# Power.net
KiCad netlist of a schematic drawn in Altium Designer
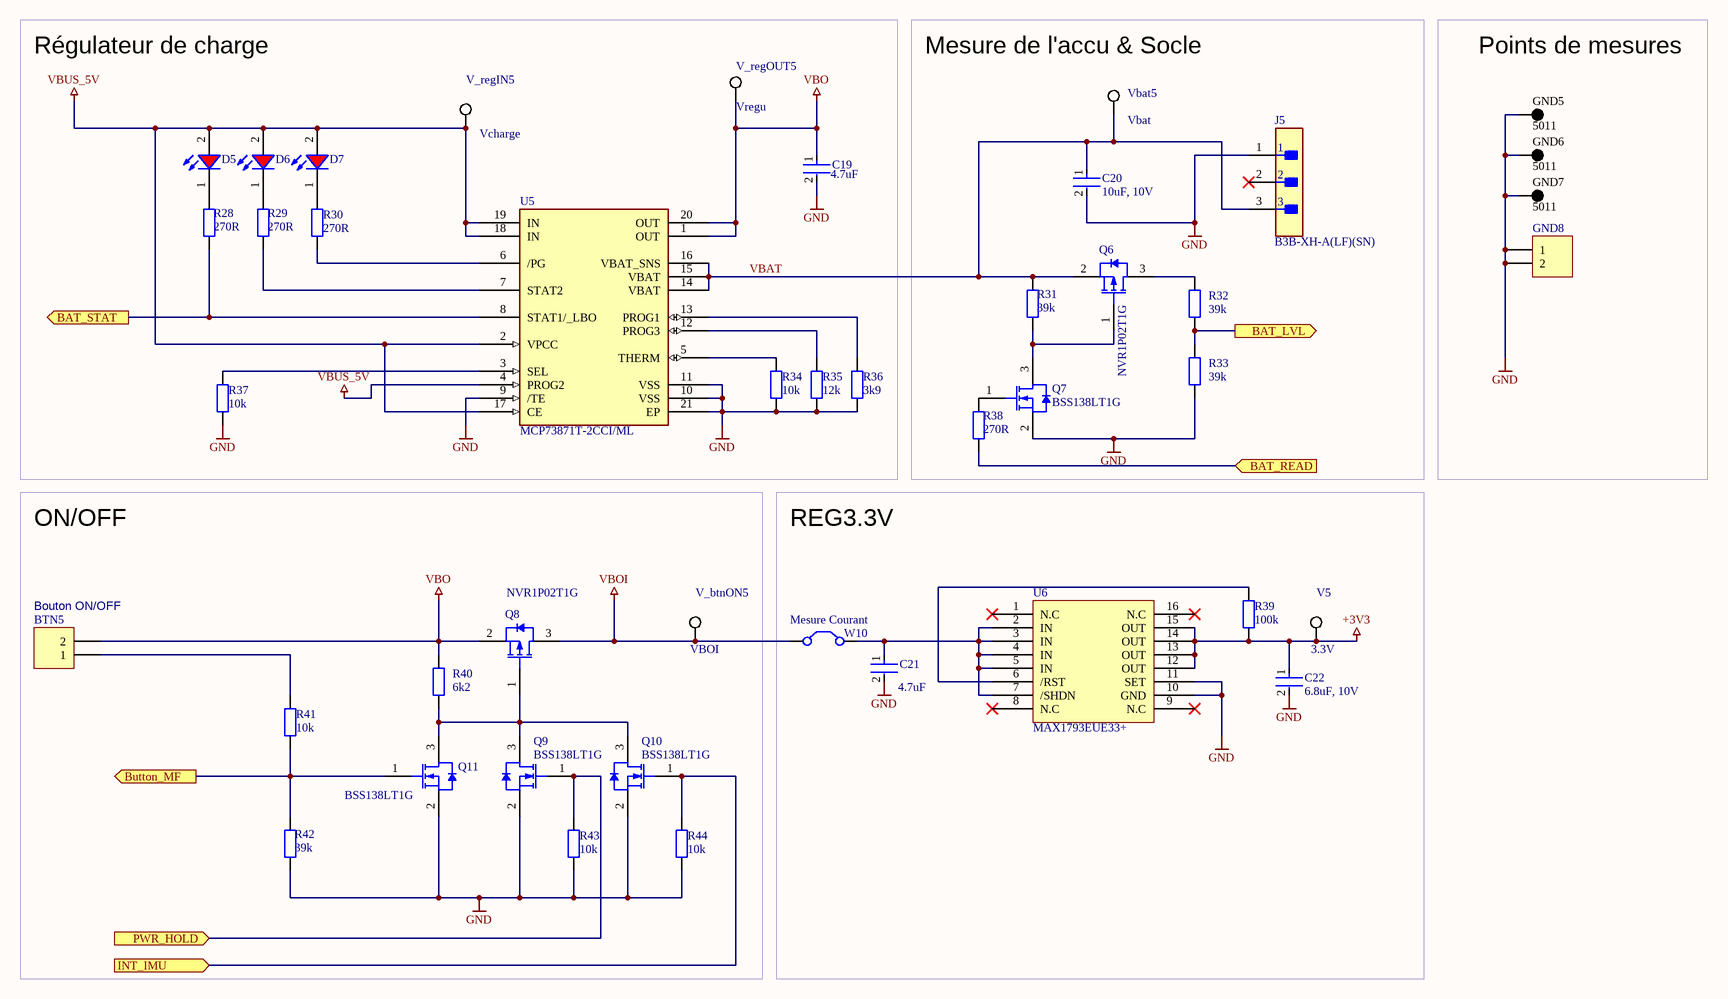
[diagram p0: Power.SchDoc]

(export (version "E")
  (design (tool "Eeschema 10.0.6"))
  (components
    (comp (ref "BTN5")
      (value "Button connector")
      (footprint "HDR1X2")
      (description "Header, 2-Pin")
      (fields (field (name "PUBLISHER") "Altium Limited"))
      (libsource (lib "") (part "Header 2_1"))
    )
    (comp (ref "C19")
      (value "4.7uF, 35V")
      (footprint "Cap_0805")
      (description "Multilayer Ceramic Capacitors 4.7μF ±10% 35V X7R SMD 0805")
      (fields (field (name "TOLERANCE") "10%") (field (name "CAPACITANCE") "4.7uF"))
      (libsource (lib "2121_Robot3roues_V2.0") (part "b4654b650e69147ec39a6b967a45e02"))
    )
    (comp (ref "C20")
      (value "10uF, 10V")
      (footprint "Cap_0805")
      (description "CAP CER 10UF 10V X5R 0805")
      (fields (field (name "TOLERANCE") "10%") (field (name "MANUFACTURER PART NUMBER") "C0805C106K8PACTU"))
      (libsource (lib "2121_Robot3roues_V2.0") (part "11868f565c42a9108669ba33697ecf6"))
    )
    (comp (ref "C21")
      (value "4.7uF, 35V")
      (footprint "Cap_0805")
      (description "Multilayer Ceramic Capacitors 4.7μF ±10% 35V X7R SMD 0805")
      (fields (field (name "TOLERANCE") "10%") (field (name "CAPACITANCE") "4.7uF"))
      (libsource (lib "2121_Robot3roues_V2.0") (part "b4654b650e69147ec39a6b967a45e02"))
    )
    (comp (ref "C22")
      (value "6.8uF, 10V")
      (footprint "Cap_0805")
      (description "Cap Ceramic 6.8uF 10V X5R 20% Pad SMD 0805 +85°C Automotive T/R")
      (fields (field (name "TOLERANCE") "20%"))
      (libsource (lib "2121_Robot3roues_V2.0") (part "b4654b650e69147ec39a6b967a45e02"))
    )
    (comp (ref "D5")
      (value "Super Red, 1.9 V")
      (footprint "WL-SMCW_0805_150080xx75000")
      (description "SMT Mono-color Chip LED Waterclear WL-SMCW, size 0805, Super Red, 1.9 V, 140 deg, 60 mcd")
      (fields (field (name "PART NUMBER") "150080SS75000") (field (name "PUBLISHER") "Wurth Elektronik"))
      (libsource (lib "VPA_v2b") (part "150080SS75000"))
    )
    (comp (ref "D6")
      (value "Super Red, 1.9 V")
      (footprint "WL-SMCW_0805_150080xx75000")
      (description "SMT Mono-color Chip LED Waterclear WL-SMCW, size 0805, Super Red, 1.9 V, 140 deg, 60 mcd")
      (fields (field (name "PART NUMBER") "150080SS75000") (field (name "PUBLISHER") "Wurth Elektronik"))
      (libsource (lib "VPA_v2b") (part "150080SS75000"))
    )
    (comp (ref "D7")
      (value "Super Red, 1.9 V")
      (footprint "WL-SMCW_0805_150080xx75000")
      (description "SMT Mono-color Chip LED Waterclear WL-SMCW, size 0805, Super Red, 1.9 V, 140 deg, 60 mcd")
      (fields (field (name "PART NUMBER") "150080SS75000") (field (name "PUBLISHER") "Wurth Elektronik"))
      (libsource (lib "VPA_v2b") (part "150080SS75000"))
    )
    (comp (ref "GND5")
      (value "5011")
      (footprint "KSTN-5011_V")
      (description "Test Point, Black, Through Hole, RoHS, Bulk")
      (fields (field (name "MANUFACTURER") "Keystone"))
      (libsource (lib "Altium Content Vault") (part "TESTPOINT_BLACK"))
    )
    (comp (ref "GND6")
      (value "5011")
      (footprint "KSTN-5011_V")
      (description "Test Point, Black, Through Hole, RoHS, Bulk")
      (fields (field (name "MANUFACTURER") "Keystone"))
      (libsource (lib "Altium Content Vault") (part "TESTPOINT_BLACK"))
    )
    (comp (ref "GND7")
      (value "5011")
      (footprint "KSTN-5011_V")
      (description "Test Point, Black, Through Hole, RoHS, Bulk")
      (fields (field (name "MANUFACTURER") "Keystone"))
      (libsource (lib "Altium Content Vault") (part "TESTPOINT_BLACK"))
    )
    (comp (ref "GND8")
      (value "Header 2")
      (footprint "HDR1X2")
      (description "Header, 2-Pin")
      (fields (field (name "PUBLISHER") "Altium Limited"))
      (libsource (lib "Miscellaneous Connectors") (part "Header 2"))
    )
    (comp (ref "J5")
      (value "B3B-XH-A(LF)(SN)")
      (footprint "FP-B3B-XH-A_LF_SN-MFG")
      (description "CONN HEADER VERT 3POS 2.5MM")
      (libsource (lib "Altium Content Vault") (part "0d3f023dd272f625e17a2be33dea85f"))
    )
    (comp (ref "Q6")
      (value "NVR1P02T1G")
      (footprint "ONSC-SOT-23-3-318-08_V")
      (description "Power MOSFET, -20 V, -1 A, P-Channel, 3-Pin SOT-23, Pb-Free, Tape and Reel")
      (fields (field (name "MANUFACTURER") "On Semiconductor"))
      (libsource (lib "Altium Content Vault") (part "ONSC-PMOS-G1S2D3-3_D"))
    )
    (comp (ref "Q7")
      (value "BSS138LT1G")
      (footprint "ONSC-SOT-23-3-318-08_V")
      (description "Power MOSFET, 200 mA, 50 V, N-Channel, 3-Pin SOT-23, Pb-Free, Tape and Reel")
      (fields (field (name "MANUFACTURER") "On Semiconductor"))
      (libsource (lib "Altium Content Vault") (part "ONSC-NMOS-G1S2D3-3"))
    )
    (comp (ref "Q8")
      (value "NVR1P02T1G")
      (footprint "ONSC-SOT-23-3-318-08_V")
      (description "Power MOSFET, -20 V, -1 A, P-Channel, 3-Pin SOT-23, Pb-Free, Tape and Reel")
      (fields (field (name "MANUFACTURER") "On Semiconductor"))
      (libsource (lib "Altium Content Vault") (part "ONSC-PMOS-G1S2D3-3_D"))
    )
    (comp (ref "Q9")
      (value "BSS138LT1G")
      (footprint "ONSC-SOT-23-3-318-08_V")
      (description "Power MOSFET, 200 mA, 50 V, N-Channel, 3-Pin SOT-23, Pb-Free, Tape and Reel")
      (fields (field (name "MANUFACTURER") "On Semiconductor"))
      (libsource (lib "Altium Content Vault") (part "ONSC-NMOS-G1S2D3-3"))
    )
    (comp (ref "Q10")
      (value "BSS138LT1G")
      (footprint "ONSC-SOT-23-3-318-08_V")
      (description "Power MOSFET, 200 mA, 50 V, N-Channel, 3-Pin SOT-23, Pb-Free, Tape and Reel")
      (fields (field (name "MANUFACTURER") "On Semiconductor"))
      (libsource (lib "Altium Content Vault") (part "ONSC-NMOS-G1S2D3-3"))
    )
    (comp (ref "Q11")
      (value "BSS138LT1G")
      (footprint "ONSC-SOT-23-3-318-08_V")
      (description "Power MOSFET, 200 mA, 50 V, N-Channel, 3-Pin SOT-23, Pb-Free, Tape and Reel")
      (fields (field (name "MANUFACTURER") "On Semiconductor"))
      (libsource (lib "Altium Content Vault") (part "ONSC-NMOS-G1S2D3-3"))
    )
    (comp (ref "R28")
      (value "270R")
      (footprint "RES_0805")
      (description "Res 0805")
      (fields (field (name "PART NUMBER") "ERJ6ENF2703V") (field (name "MANUFACTURER") "Panasonic"))
      (libsource (lib "2121_Robot3roues_V2.0") (part "RES"))
    )
    (comp (ref "R29")
      (value "270R")
      (footprint "RES_0805")
      (description "Res 0805")
      (fields (field (name "PART NUMBER") "ERJ6ENF2703V") (field (name "MANUFACTURER") "Panasonic"))
      (libsource (lib "2121_Robot3roues_V2.0") (part "RES"))
    )
    (comp (ref "R30")
      (value "270R")
      (footprint "RES_0805")
      (description "Res 0805")
      (fields (field (name "PART NUMBER") "ERJ6ENF2703V") (field (name "MANUFACTURER") "Panasonic"))
      (libsource (lib "") (part "RES_1"))
    )
    (comp (ref "R31")
      (value "39k")
      (footprint "RES_0805")
      (description "Res 0805")
      (fields (field (name "PART NUMBER") "ERJ-6GEYJ393V") (field (name "MANUFACTURER") "Panasonic"))
      (libsource (lib "2121_Robot3roues_V2.0") (part "RES"))
    )
    (comp (ref "R32")
      (value "39k")
      (footprint "RES_0805")
      (description "Res 0805")
      (fields (field (name "PART NUMBER") "ERJ-6GEYJ393V") (field (name "MANUFACTURER") "Panasonic"))
      (libsource (lib "2121_Robot3roues_V2.0") (part "RES"))
    )
    (comp (ref "R33")
      (value "39k")
      (footprint "RES_0805")
      (description "Res 0805")
      (fields (field (name "PART NUMBER") "ERJ-6GEYJ393V") (field (name "MANUFACTURER") "Panasonic"))
      (libsource (lib "2121_Robot3roues_V2.0") (part "RES"))
    )
    (comp (ref "R34")
      (value "10k")
      (footprint "RES_0805")
      (description "Res 0805")
      (fields (field (name "MANUFACTURER") "Panasonic") (field (name "PART NUMBER") "ERJ-6ENF1002V"))
      (libsource (lib "2121_Robot3roues_V2.0") (part "RES"))
    )
    (comp (ref "R35")
      (value "12k")
      (footprint "RES_0805")
      (description "Res 0805")
      (fields (field (name "MANUFACTURER") "Vishay Dale") (field (name "PART NUMBER") "CRCW08055K60JNEA"))
      (libsource (lib "2121_Robot3roues_V2.0") (part "RES"))
    )
    (comp (ref "R36")
      (value "3k9")
      (footprint "RES_0805")
      (description "Res 0805")
      (fields (field (name "PART NUMBER") "CRCW08051K00FKEA") (field (name "MANUFACTURER") "Vishay Dale"))
      (libsource (lib "2121_Robot3roues_V2.0") (part "RES"))
    )
    (comp (ref "R37")
      (value "10k")
      (footprint "RES_0805")
      (description "Res 0805")
      (fields (field (name "MANUFACTURER") "Panasonic") (field (name "PART NUMBER") "ERJ-6ENF1002V"))
      (libsource (lib "2121_Robot3roues_V2.0") (part "RES"))
    )
    (comp (ref "R38")
      (value "270R")
      (footprint "RES_0805")
      (description "Res 0805")
      (fields (field (name "PART NUMBER") "ERJ6ENF2703V") (field (name "MANUFACTURER") "Panasonic"))
      (libsource (lib "2121_Robot3roues_V2.0") (part "RES"))
    )
    (comp (ref "R39")
      (value "100k")
      (footprint "RES_0805")
      (description "Res 0805")
      (fields (field (name "MANUFACTURER") "Panasonic") (field (name "PART NUMBER") "ERJ-P06J104V"))
      (libsource (lib "2121_Robot3roues_V2.0") (part "RES"))
    )
    (comp (ref "R40")
      (value "6k2")
      (footprint "RES_0805")
      (description "Res 0805")
      (fields (field (name "PART NUMBER") "ERJ6ENF6201V") (field (name "MANUFACTURER") "Panasonic"))
      (libsource (lib "2121_Robot3roues_V2.0") (part "RES"))
    )
    (comp (ref "R41")
      (value "10k")
      (footprint "RES_0805")
      (description "Res 0805")
      (fields (field (name "MANUFACTURER") "Panasonic") (field (name "PART NUMBER") "ERJ-6ENF1002V"))
      (libsource (lib "2121_Robot3roues_V2.0") (part "RES"))
    )
    (comp (ref "R42")
      (value "39k")
      (footprint "RES_0805")
      (description "Res 0805")
      (fields (field (name "PART NUMBER") "ERJ-6GEYJ393V") (field (name "MANUFACTURER") "Panasonic"))
      (libsource (lib "2121_Robot3roues_V2.0") (part "RES"))
    )
    (comp (ref "R43")
      (value "10k")
      (footprint "RES_0805")
      (description "Res 0805")
      (fields (field (name "MANUFACTURER") "Panasonic") (field (name "PART NUMBER") "ERJ-6ENF1002V"))
      (libsource (lib "2121_Robot3roues_V2.0") (part "RES"))
    )
    (comp (ref "R44")
      (value "10k")
      (footprint "RES_0805")
      (description "Res 0805")
      (fields (field (name "MANUFACTURER") "Panasonic") (field (name "PART NUMBER") "ERJ-6ENF1002V"))
      (libsource (lib "2121_Robot3roues_V2.0") (part "RES"))
    )
    (comp (ref "U5")
      (value "MCP73871T-2CCI/ML")
      (footprint "Microchip_C04-126_IPC_B")
      (description "Charger IC Lithium Ion/Polymer 20-QFN _4x4_")
      (fields (field (name "MF") "Microchip") (field (name "DIGI-KEY_PART_NUMBER") "MCP73871T-2CCI/MLCT-ND"))
      (libsource (lib "2221-LIB") (part "MCP73871T-2CCI/ML"))
    )
    (comp (ref "U6")
      (value "MAX1793EUE33+")
      (footprint "TSOP65P640X110_HS-17N")
      (libsource (lib "2221-LIB") (part "MAX1793EUE33+"))
    )
    (comp (ref "V5")
      (value "3.3V")
      (footprint "KSTN-5019_V")
      (description "Test Point, 1 Position SMD, RoHS, Tape and Reel")
      (libsource (lib "Altium Content Vault") (part "TESTPOINT_WHITE"))
    )
    (comp (ref "Vbat5")
      (value "Vbat")
      (footprint "KSTN-5019_V")
      (description "Test Point, 1 Position SMD, RoHS, Tape and Reel")
      (libsource (lib "Altium Content Vault") (part "TESTPOINT_WHITE"))
    )
    (comp (ref "V_btnON5")
      (value "VBOI")
      (footprint "KSTN-5019_V")
      (description "Test Point, 1 Position SMD, RoHS, Tape and Reel")
      (libsource (lib "Altium Content Vault") (part "TESTPOINT_WHITE"))
    )
    (comp (ref "V_regIN5")
      (value "Vcharge")
      (footprint "KSTN-5019_V")
      (description "Test Point, 1 Position SMD, RoHS, Tape and Reel")
      (libsource (lib "Altium Content Vault") (part "TESTPOINT_WHITE"))
    )
    (comp (ref "V_regOUT5")
      (value "Vregu")
      (footprint "KSTN-5019_V")
      (description "Test Point, 1 Position SMD, RoHS, Tape and Reel")
      (libsource (lib "Altium Content Vault") (part "TESTPOINT_WHITE"))
    )
    (comp (ref "W10")
      (value "Jumper")
      (footprint "JUMPER")
      (description "Jumper Wire")
      (fields (field (name "PUBLISHER") "Altium Limited"))
      (libsource (lib "Miscellaneous Devices") (part "Jumper"))
    )
  )
  (nets
    (net (code "1") (name "+3V3") (class "Default")
      (node (ref "C22") (pin "1") (pinfunction "1_1") (pintype "passive"))
      (node (ref "R39") (pin "1") (pinfunction "1_1") (pintype "passive"))
      (node (ref "U6") (pin "12") (pinfunction "OUT_12") (pintype "passive"))
      (node (ref "U6") (pin "13") (pinfunction "OUT_13") (pintype "passive"))
      (node (ref "U6") (pin "14") (pinfunction "OUT_14") (pintype "passive"))
      (node (ref "U6") (pin "15") (pinfunction "OUT_15") (pintype "passive"))
      (node (ref "V5") (pin "1") (pinfunction "1_1") (pintype "passive"))
    )
    (net (code "2") (name "/BAT_LVL") (class "Default")
      (node (ref "R32") (pin "1") (pinfunction "1_1") (pintype "passive"))
      (node (ref "R33") (pin "2") (pinfunction "2_2") (pintype "passive"))
    )
    (net (code "3") (name "/BAT_READ") (class "Default")
      (node (ref "R38") (pin "1") (pinfunction "1_1") (pintype "passive"))
    )
    (net (code "4") (name "/BAT_STAT") (class "Default")
      (node (ref "R28") (pin "1") (pinfunction "1_1") (pintype "passive"))
      (node (ref "U5") (pin "8") (pinfunction "STAT1/_LBO_8") (pintype "passive"))
    )
    (net (code "5") (name "/Button_MF") (class "Default")
      (node (ref "Q11") (pin "1") (pinfunction "G_1") (pintype "passive"))
      (node (ref "R41") (pin "1") (pinfunction "1_1") (pintype "passive"))
      (node (ref "R42") (pin "2") (pinfunction "2_2") (pintype "passive"))
    )
    (net (code "6") (name "/INT_IMU") (class "Default")
      (node (ref "Q10") (pin "1") (pinfunction "G_1") (pintype "passive"))
      (node (ref "R44") (pin "2") (pinfunction "2_2") (pintype "passive"))
    )
    (net (code "7") (name "/PWR_HOLD") (class "Default")
      (node (ref "Q9") (pin "1") (pinfunction "G_1") (pintype "passive"))
      (node (ref "R43") (pin "2") (pinfunction "2_2") (pintype "passive"))
    )
    (net (code "8") (name "/VBAT") (class "Default")
      (node (ref "C20") (pin "1") (pinfunction "1_1") (pintype "passive"))
      (node (ref "J5") (pin "3") (pinfunction "3_3") (pintype "passive"))
      (node (ref "Q6") (pin "2") (pinfunction "S_2") (pintype "passive"))
      (node (ref "R31") (pin "2") (pinfunction "2_2") (pintype "passive"))
      (node (ref "U5") (pin "14") (pinfunction "VBAT_14") (pintype "passive"))
      (node (ref "U5") (pin "15") (pinfunction "VBAT_15") (pintype "passive"))
      (node (ref "U5") (pin "16") (pinfunction "VBAT_SNS_16") (pintype "passive"))
      (node (ref "Vbat5") (pin "1") (pinfunction "1_1") (pintype "passive"))
    )
    (net (code "9") (name "GND") (class "Default")
      (node (ref "C19") (pin "2") (pinfunction "2_2") (pintype "passive"))
      (node (ref "C20") (pin "2") (pinfunction "2_2") (pintype "passive"))
      (node (ref "C21") (pin "2") (pinfunction "2_2") (pintype "passive"))
      (node (ref "C22") (pin "2") (pinfunction "2_2") (pintype "passive"))
      (node (ref "GND5") (pin "1") (pinfunction "1_1") (pintype "passive"))
      (node (ref "GND6") (pin "1") (pinfunction "1_1") (pintype "passive"))
      (node (ref "GND7") (pin "1") (pinfunction "1_1") (pintype "passive"))
      (node (ref "GND8") (pin "1") (pinfunction "1_1") (pintype "passive"))
      (node (ref "GND8") (pin "2") (pinfunction "2_2") (pintype "passive"))
      (node (ref "J5") (pin "1") (pinfunction "1_1") (pintype "passive"))
      (node (ref "Q10") (pin "2") (pinfunction "S_2") (pintype "passive"))
      (node (ref "Q11") (pin "2") (pinfunction "S_2") (pintype "passive"))
      (node (ref "Q7") (pin "2") (pinfunction "S_2") (pintype "passive"))
      (node (ref "Q9") (pin "2") (pinfunction "S_2") (pintype "passive"))
      (node (ref "R33") (pin "1") (pinfunction "1_1") (pintype "passive"))
      (node (ref "R34") (pin "1") (pinfunction "1_1") (pintype "passive"))
      (node (ref "R35") (pin "1") (pinfunction "1_1") (pintype "passive"))
      (node (ref "R36") (pin "1") (pinfunction "1_1") (pintype "passive"))
      (node (ref "R37") (pin "1") (pinfunction "1_1") (pintype "passive"))
      (node (ref "R42") (pin "1") (pinfunction "1_1") (pintype "passive"))
      (node (ref "R43") (pin "1") (pinfunction "1_1") (pintype "passive"))
      (node (ref "R44") (pin "1") (pinfunction "1_1") (pintype "passive"))
      (node (ref "U5") (pin "10") (pinfunction "VSS_10") (pintype "passive"))
      (node (ref "U5") (pin "11") (pinfunction "VSS_11") (pintype "passive"))
      (node (ref "U5") (pin "21") (pinfunction "EP_21") (pintype "passive"))
      (node (ref "U5") (pin "9") (pinfunction "/TE_9") (pintype "input"))
      (node (ref "U6") (pin "10") (pinfunction "GND_10") (pintype "passive"))
      (node (ref "U6") (pin "11") (pinfunction "SET_11") (pintype "passive"))
    )
    (net (code "10") (name "Net-(BTN5-Pad1)") (class "Default")
      (node (ref "BTN5") (pin "1") (pinfunction "1_1") (pintype "passive"))
      (node (ref "R41") (pin "2") (pinfunction "2_2") (pintype "passive"))
    )
    (net (code "11") (name "Net-(D5-K)") (class "Default")
      (node (ref "D5") (pin "1") (pinfunction "K_1") (pintype "passive"))
      (node (ref "R28") (pin "2") (pinfunction "2_2") (pintype "passive"))
    )
    (net (code "12") (name "Net-(D6-K)") (class "Default")
      (node (ref "D6") (pin "1") (pinfunction "K_1") (pintype "passive"))
      (node (ref "R29") (pin "2") (pinfunction "2_2") (pintype "passive"))
    )
    (net (code "13") (name "Net-(D7-K)") (class "Default")
      (node (ref "D7") (pin "1") (pinfunction "K_1") (pintype "passive"))
      (node (ref "R30") (pin "1") (pinfunction "1_1") (pintype "passive"))
    )
    (net (code "14") (name "Net-(Q6-D)") (class "Default")
      (node (ref "Q6") (pin "3") (pinfunction "D_3") (pintype "passive"))
      (node (ref "R32") (pin "2") (pinfunction "2_2") (pintype "passive"))
    )
    (net (code "15") (name "Net-(Q6-G)") (class "Default")
      (node (ref "Q6") (pin "1") (pinfunction "G_1") (pintype "passive"))
      (node (ref "Q7") (pin "3") (pinfunction "D_3") (pintype "passive"))
      (node (ref "R31") (pin "1") (pinfunction "1_1") (pintype "passive"))
    )
    (net (code "16") (name "Net-(Q7-G)") (class "Default")
      (node (ref "Q7") (pin "1") (pinfunction "G_1") (pintype "passive"))
      (node (ref "R38") (pin "2") (pinfunction "2_2") (pintype "passive"))
    )
    (net (code "17") (name "Net-(Q10-D)") (class "Default")
      (node (ref "Q10") (pin "3") (pinfunction "D_3") (pintype "passive"))
      (node (ref "Q11") (pin "3") (pinfunction "D_3") (pintype "passive"))
      (node (ref "Q8") (pin "1") (pinfunction "G_1") (pintype "passive"))
      (node (ref "Q9") (pin "3") (pinfunction "D_3") (pintype "passive"))
      (node (ref "R40") (pin "1") (pinfunction "1_1") (pintype "passive"))
    )
    (net (code "18") (name "Net-(U5-PROG1)") (class "Default")
      (node (ref "R36") (pin "2") (pinfunction "2_2") (pintype "passive"))
      (node (ref "U5") (pin "13") (pinfunction "PROG1_13") (pintype "bidirectional"))
    )
    (net (code "19") (name "Net-(U5-PROG3)") (class "Default")
      (node (ref "R35") (pin "2") (pinfunction "2_2") (pintype "passive"))
      (node (ref "U5") (pin "12") (pinfunction "PROG3_12") (pintype "bidirectional"))
    )
    (net (code "20") (name "Net-(U5-SEL)") (class "Default")
      (node (ref "R37") (pin "2") (pinfunction "2_2") (pintype "passive"))
      (node (ref "U5") (pin "3") (pinfunction "SEL_3") (pintype "input"))
    )
    (net (code "21") (name "Net-(U5-STAT2)") (class "Default")
      (node (ref "R29") (pin "1") (pinfunction "1_1") (pintype "passive"))
      (node (ref "U5") (pin "7") (pinfunction "STAT2_7") (pintype "passive"))
    )
    (net (code "22") (name "Net-(U5-THERM)") (class "Default")
      (node (ref "R34") (pin "2") (pinfunction "2_2") (pintype "passive"))
      (node (ref "U5") (pin "5") (pinfunction "THERM_5") (pintype "bidirectional"))
    )
    (net (code "23") (name "Net-(U5-{slash}PG)") (class "Default")
      (node (ref "R30") (pin "2") (pinfunction "2_2") (pintype "passive"))
      (node (ref "U5") (pin "6") (pinfunction "/PG_6") (pintype "passive"))
    )
    (net (code "24") (name "Net-(U6-{slash}RST)") (class "Default")
      (node (ref "R39") (pin "2") (pinfunction "2_2") (pintype "passive"))
      (node (ref "U6") (pin "6") (pinfunction "/RST_6") (pintype "passive"))
    )
    (net (code "25") (name "Net-(U6-{slash}SHDN)") (class "Default")
      (node (ref "C21") (pin "1") (pinfunction "1_1") (pintype "passive"))
      (node (ref "U6") (pin "2") (pinfunction "IN_2") (pintype "passive"))
      (node (ref "U6") (pin "3") (pinfunction "IN_3") (pintype "passive"))
      (node (ref "U6") (pin "4") (pinfunction "IN_4") (pintype "passive"))
      (node (ref "U6") (pin "5") (pinfunction "IN_5") (pintype "passive"))
      (node (ref "U6") (pin "7") (pinfunction "/SHDN_7") (pintype "passive"))
      (node (ref "W10") (pin "2") (pinfunction "C2_2") (pintype "passive"))
    )
    (net (code "26") (name "VBO") (class "Default")
      (node (ref "BTN5") (pin "2") (pinfunction "2_2") (pintype "passive"))
      (node (ref "C19") (pin "1") (pinfunction "1_1") (pintype "passive"))
      (node (ref "Q8") (pin "2") (pinfunction "S_2") (pintype "passive"))
      (node (ref "R40") (pin "2") (pinfunction "2_2") (pintype "passive"))
      (node (ref "U5") (pin "1") (pinfunction "OUT_1") (pintype "passive"))
      (node (ref "U5") (pin "20") (pinfunction "OUT_20") (pintype "passive"))
      (node (ref "V_regOUT5") (pin "1") (pinfunction "1_1") (pintype "passive"))
    )
    (net (code "27") (name "VBOI") (class "Default")
      (node (ref "Q8") (pin "3") (pinfunction "D_3") (pintype "passive"))
      (node (ref "V_btnON5") (pin "1") (pinfunction "1_1") (pintype "passive"))
      (node (ref "W10") (pin "1") (pinfunction "C1_1") (pintype "passive"))
    )
    (net (code "28") (name "VBUS_5V") (class "Default")
      (node (ref "D5") (pin "2") (pinfunction "A_2") (pintype "passive"))
      (node (ref "D6") (pin "2") (pinfunction "A_2") (pintype "passive"))
      (node (ref "D7") (pin "2") (pinfunction "A_2") (pintype "passive"))
      (node (ref "U5") (pin "17") (pinfunction "CE_17") (pintype "input"))
      (node (ref "U5") (pin "18") (pinfunction "IN_18") (pintype "passive"))
      (node (ref "U5") (pin "19") (pinfunction "IN_19") (pintype "passive"))
      (node (ref "U5") (pin "2") (pinfunction "VPCC_2") (pintype "input"))
      (node (ref "U5") (pin "4") (pinfunction "PROG2_4") (pintype "input"))
      (node (ref "V_regIN5") (pin "1") (pinfunction "1_1") (pintype "passive"))
    )
    (net (code "29") (name "unconnected-(J5-Pad2)") (class "Default")
      (node (ref "J5") (pin "2") (pinfunction "2_2") (pintype "passive+no_connect"))
    )
    (net (code "30") (name "unconnected-(U6-N.C-Pad1)") (class "Default")
      (node (ref "U6") (pin "1") (pinfunction "N.C_1") (pintype "passive+no_connect"))
    )
    (net (code "31") (name "unconnected-(U6-N.C-Pad8)") (class "Default")
      (node (ref "U6") (pin "8") (pinfunction "N.C_8") (pintype "passive+no_connect"))
    )
    (net (code "32") (name "unconnected-(U6-N.C-Pad9)") (class "Default")
      (node (ref "U6") (pin "9") (pinfunction "N.C_9") (pintype "passive+no_connect"))
    )
    (net (code "33") (name "unconnected-(U6-N.C-Pad16)") (class "Default")
      (node (ref "U6") (pin "16") (pinfunction "N.C_16") (pintype "passive+no_connect"))
    )
  )
)
